# ILIZAROV_2.net
KiCad netlist of a schematic drawn in EAGLE
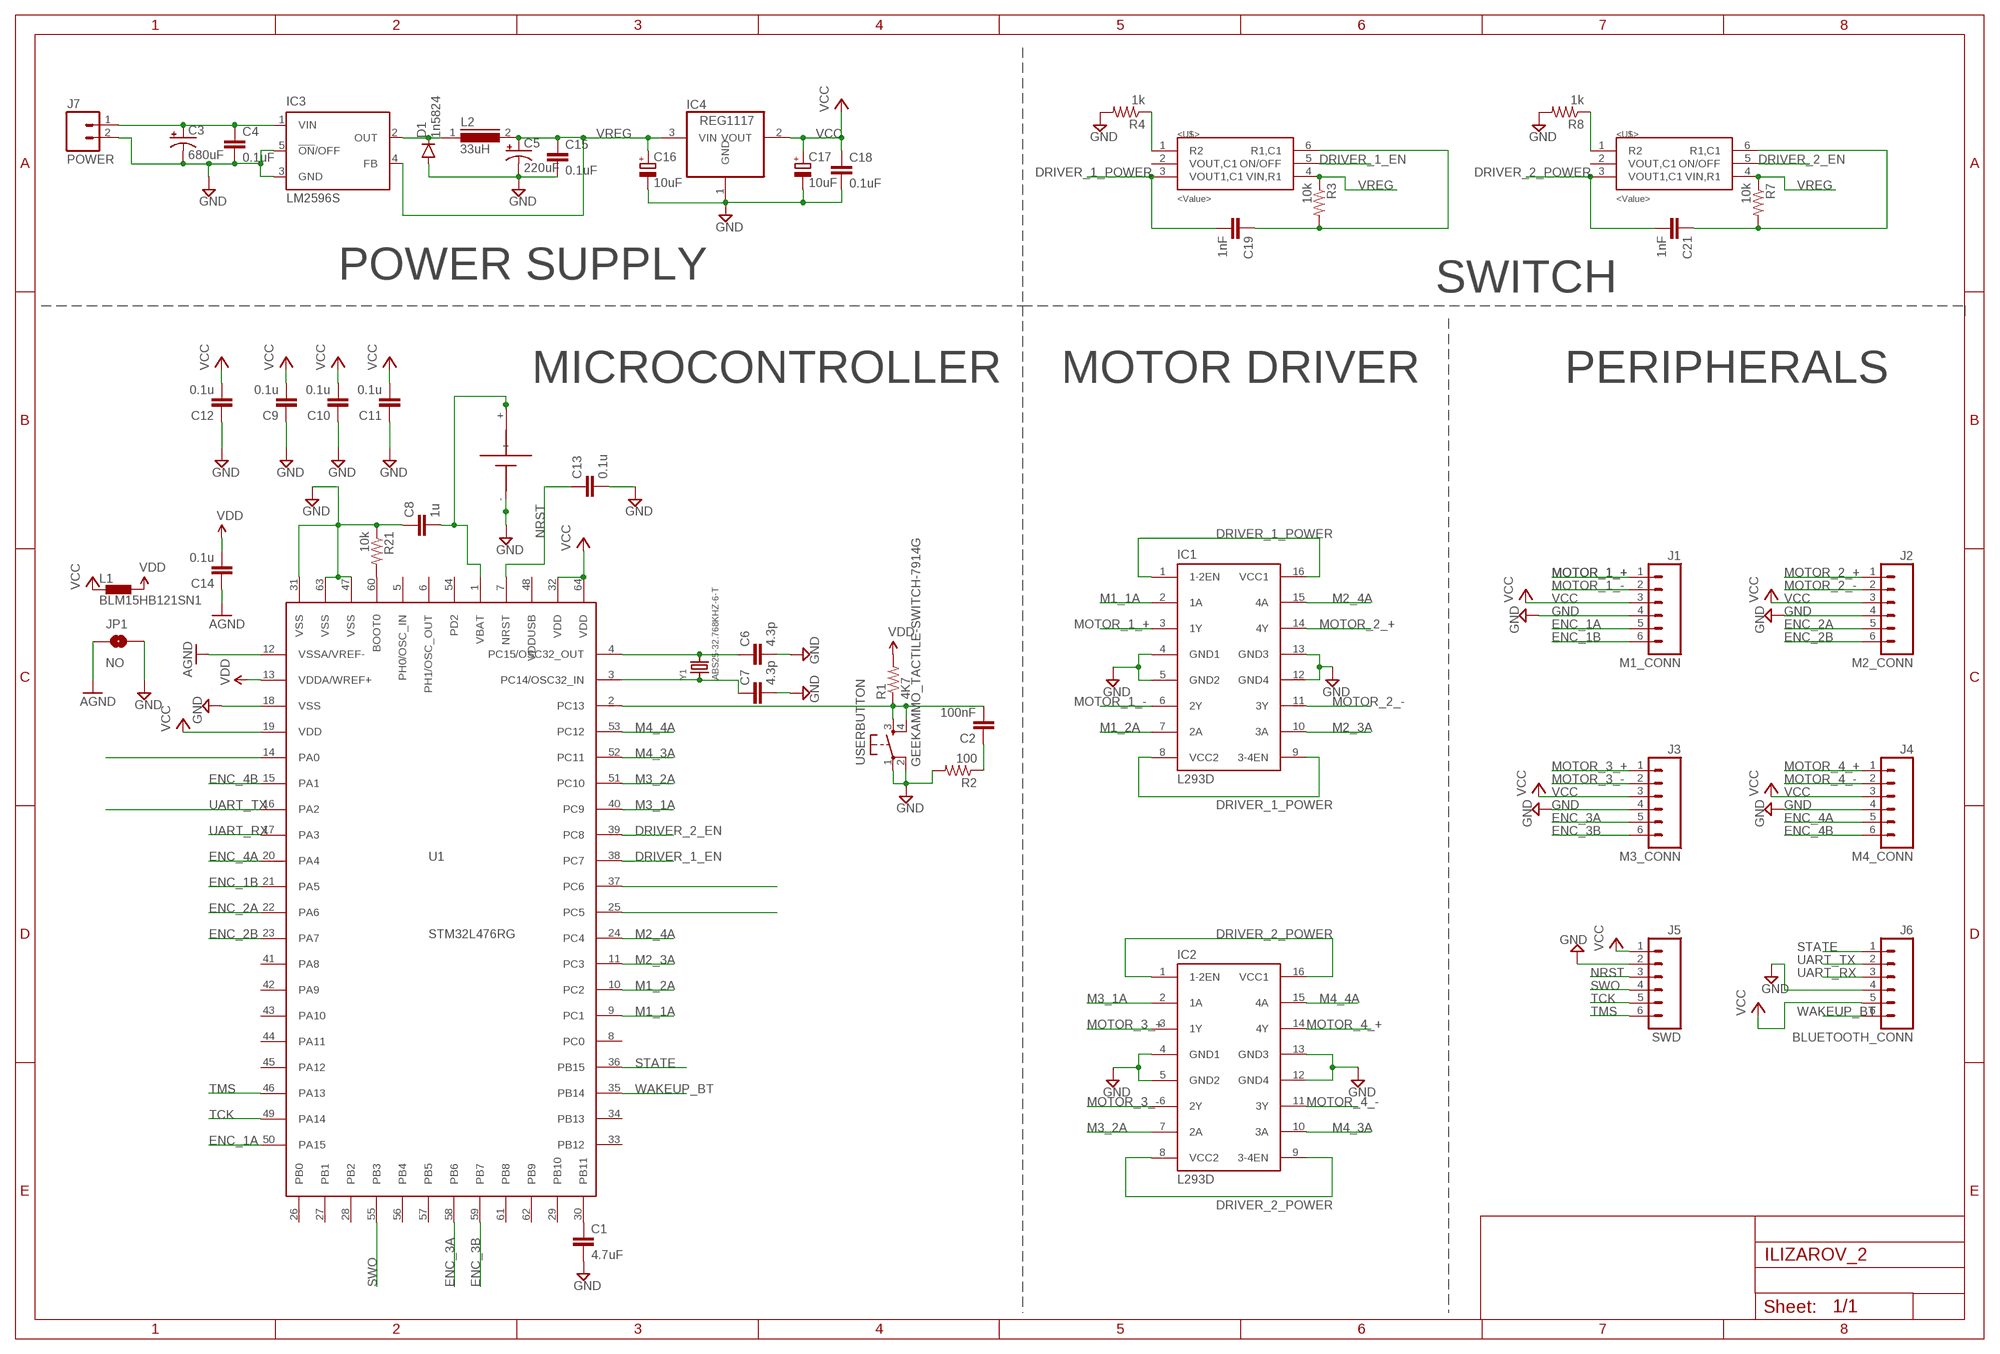
[diagram p0: schematic, sheet 1]

(export (version "E")
  (design (tool "Eeschema 10.0.6"))
  (components
    (comp (ref "BLUETOOTH_CONN")
      (value "J6")
      (footprint "eagle-import:06P")
      (libsource (lib "eagle-import") (part "M06"))
    )
    (comp (ref "C1")
      (value "4.7uF")
      (footprint "eagle-import:1206")
      (libsource (lib "eagle-import") (part "CAP1206"))
    )
    (comp (ref "C2")
      (value "100nF")
      (footprint "eagle-import:C0805")
      (libsource (lib "eagle-import") (part "C-EUC0805"))
    )
    (comp (ref "C3")
      (value "680uF")
      (footprint "eagle-import:140CLH-1010")
      (libsource (lib "eagle-import") (part "CPOL-US140CLH-1010"))
    )
    (comp (ref "C4")
      (value "0.1uF")
      (footprint "eagle-import:SPARKFUN-CAPACITORS_1206")
      (libsource (lib "eagle-import") (part "SPARKFUN-CAPACITORS_CAP1206"))
    )
    (comp (ref "C5")
      (value "220uF")
      (footprint "eagle-import:140CLH-1010")
      (libsource (lib "eagle-import") (part "CPOL-US140CLH-1010"))
    )
    (comp (ref "C6")
      (value "4.3p")
      (footprint "eagle-import:C0805")
      (libsource (lib "eagle-import") (part "C-EUC0805"))
    )
    (comp (ref "C7")
      (value "4.3p")
      (footprint "eagle-import:C0805")
      (libsource (lib "eagle-import") (part "C-EUC0805"))
    )
    (comp (ref "C8")
      (value "1u")
      (footprint "eagle-import:C0805")
      (libsource (lib "eagle-import") (part "C-EUC0805"))
    )
    (comp (ref "C9")
      (value "0.1u")
      (footprint "eagle-import:C0805")
      (libsource (lib "eagle-import") (part "C-EUC0805"))
    )
    (comp (ref "C10")
      (value "0.1u")
      (footprint "eagle-import:C0805")
      (libsource (lib "eagle-import") (part "C-EUC0805"))
    )
    (comp (ref "C11")
      (value "0.1u")
      (footprint "eagle-import:C0805")
      (libsource (lib "eagle-import") (part "C-EUC0805"))
    )
    (comp (ref "C12")
      (value "0.1u")
      (footprint "eagle-import:C0805")
      (libsource (lib "eagle-import") (part "C-EUC0805"))
    )
    (comp (ref "C13")
      (value "0.1u")
      (footprint "eagle-import:C0805")
      (libsource (lib "eagle-import") (part "C-EUC0805"))
    )
    (comp (ref "C14")
      (value "0.1u")
      (footprint "eagle-import:C0805")
      (libsource (lib "eagle-import") (part "C-EUC0805"))
    )
    (comp (ref "C15")
      (value "0.1uF")
      (footprint "eagle-import:SPARKFUN-CAPACITORS_1206")
      (libsource (lib "eagle-import") (part "SPARKFUN-CAPACITORS_CAP1206"))
    )
    (comp (ref "C16")
      (value "10uF")
      (footprint "eagle-import:SMC_C")
      (libsource (lib "eagle-import") (part "CPOL-EUSMCC"))
    )
    (comp (ref "C17")
      (value "10uF")
      (footprint "eagle-import:SMC_C")
      (libsource (lib "eagle-import") (part "CPOL-EUSMCC"))
    )
    (comp (ref "C18")
      (value "0.1uF")
      (footprint "eagle-import:SPARKFUN-CAPACITORS_1206")
      (libsource (lib "eagle-import") (part "SPARKFUN-CAPACITORS_CAP1206"))
    )
    (comp (ref "C19")
      (value "1nF")
      (footprint "eagle-import:C1206")
      (libsource (lib "eagle-import") (part "C-EUC1206"))
    )
    (comp (ref "C21")
      (value "1nF")
      (footprint "eagle-import:C1206")
      (libsource (lib "eagle-import") (part "C-EUC1206"))
    )
    (comp (ref "D1")
      (value "1n5824")
      (footprint "eagle-import:SPARKFUN-DISCRETESEMI_SOD-123")
      (libsource (lib "eagle-import") (part "SPARKFUN-DISCRETESEMI_DIODESOD123"))
    )
    (comp (ref "IC1")
      (value "L293D")
      (footprint "eagle-import:DIL16")
      (libsource (lib "eagle-import") (part "L293D"))
    )
    (comp (ref "IC2")
      (value "L293D")
      (footprint "eagle-import:DIL16")
      (libsource (lib "eagle-import") (part "L293D"))
    )
    (comp (ref "IC3")
      (value "LM2596S")
      (footprint "eagle-import:TO263-5")
      (fields (field (name "MF") "NATIONAL SEMICONDUCTOR") (field (name "MPN") "LM2596S-ADJ/NOPB"))
      (libsource (lib "eagle-import") (part "LM2596S"))
    )
    (comp (ref "IC4")
      (value "REG1117")
      (footprint "eagle-import:SOT223")
      (libsource (lib "eagle-import") (part "REG1117"))
    )
    (comp (ref "JP1")
      (value "NO")
      (footprint "eagle-import:PAD-JUMPER-2-NO_NO_SILK")
      (libsource (lib "eagle-import") (part "JUMPER-PAD-2-NO"))
    )
    (comp (ref "L1")
      (value "BLM15HB121SN1")
      (footprint "eagle-import:0402")
      (libsource (lib "eagle-import") (part "BLM15HB121SN1"))
    )
    (comp (ref "L2")
      (value "33uH")
      (footprint "eagle-import:DR125")
      (libsource (lib "eagle-import") (part "DR125"))
    )
    (comp (ref "M1_CONN")
      (value "J1")
      (footprint "eagle-import:06P")
      (libsource (lib "eagle-import") (part "M06"))
    )
    (comp (ref "M2_CONN")
      (value "J2")
      (footprint "eagle-import:06P")
      (libsource (lib "eagle-import") (part "M06"))
    )
    (comp (ref "M3_CONN")
      (value "J3")
      (footprint "eagle-import:06P")
      (libsource (lib "eagle-import") (part "M06"))
    )
    (comp (ref "M4_CONN")
      (value "J4")
      (footprint "eagle-import:06P")
      (libsource (lib "eagle-import") (part "M06"))
    )
    (comp (ref "POWER")
      (value "J7")
      (footprint "eagle-import:02P")
      (libsource (lib "eagle-import") (part "M02"))
    )
    (comp (ref "R1")
      (value "4K7")
      (footprint "eagle-import:1206")
      (libsource (lib "eagle-import") (part "RESISTOR1206"))
    )
    (comp (ref "R2")
      (value "100")
      (footprint "eagle-import:1206")
      (libsource (lib "eagle-import") (part "RESISTOR1206"))
    )
    (comp (ref "R3")
      (value "10k")
      (footprint "eagle-import:1206")
      (libsource (lib "eagle-import") (part "RESISTOR1206"))
    )
    (comp (ref "R4")
      (value "1k")
      (footprint "eagle-import:1206")
      (libsource (lib "eagle-import") (part "RESISTOR1206"))
    )
    (comp (ref "R7")
      (value "10k")
      (footprint "eagle-import:1206")
      (libsource (lib "eagle-import") (part "RESISTOR1206"))
    )
    (comp (ref "R8")
      (value "1k")
      (footprint "eagle-import:1206")
      (libsource (lib "eagle-import") (part "RESISTOR1206"))
    )
    (comp (ref "R21")
      (value "10k")
      (footprint "eagle-import:M0805")
      (libsource (lib "eagle-import") (part "R-US_M0805"))
    )
    (comp (ref "SWD")
      (value "J5")
      (footprint "eagle-import:06P")
      (libsource (lib "eagle-import") (part "M06"))
    )
    (comp (ref "U$1")
      (value "MS920")
      (footprint "eagle-import:SMD")
      (libsource (lib "eagle-import") (part "MS920"))
    )
    (comp (ref "U$6")
      (value "FDC6330L")
      (footprint "eagle-import:SOT23-6")
      (libsource (lib "eagle-import") (part "FDC6330L"))
    )
    (comp (ref "U$7")
      (value "FDC6330L")
      (footprint "eagle-import:SOT23-6")
      (libsource (lib "eagle-import") (part "FDC6330L"))
    )
    (comp (ref "U1")
      (value "STM32L476RG")
      (footprint "eagle-import:LQFP-10X10-64")
      (libsource (lib "eagle-import") (part "STM32L476RG"))
    )
    (comp (ref "USERBUTTON")
      (value "GEEKAMMO_TACTILE-SWITCH-7914G")
      (footprint "eagle-import:GEEKAMMO_7914G")
      (libsource (lib "eagle-import") (part "GEEKAMMO_TACTILE-SWITCH-7914G"))
    )
    (comp (ref "Y1")
      (value "ABS25-32.768KHZ-6-T")
      (footprint "eagle-import:ABS25")
      (libsource (lib "eagle-import") (part "CRYSTAL.ABS25"))
    )
  )
  (nets
    (net (code "1") (name "/DRIVER_1_EN") (class "Default")
      (node (ref "U$7") (pin "5") (pinfunction "ON/OFF_5") (pintype "bidirectional"))
      (node (ref "U1") (pin "38") (pinfunction "PC7_38") (pintype "bidirectional"))
    )
    (net (code "2") (name "/DRIVER_1_POWER") (class "Default")
      (node (ref "C19") (pin "2") (pinfunction "2_2") (pintype "passive"))
      (node (ref "IC1") (pin "1") (pinfunction "1-2EN_1") (pintype "input"))
      (node (ref "IC1") (pin "16") (pinfunction "VCC1_16") (pintype "power_in"))
      (node (ref "IC1") (pin "8") (pinfunction "VCC2_8") (pintype "power_in"))
      (node (ref "IC1") (pin "9") (pinfunction "3-4EN_9") (pintype "input"))
      (node (ref "U$7") (pin "3") (pinfunction "VOUT1,C1_3") (pintype "bidirectional"))
    )
    (net (code "3") (name "/DRIVER_2_EN") (class "Default")
      (node (ref "U$6") (pin "5") (pinfunction "ON/OFF_5") (pintype "bidirectional"))
      (node (ref "U1") (pin "39") (pinfunction "PC8_39") (pintype "bidirectional"))
    )
    (net (code "4") (name "/DRIVER_2_POWER") (class "Default")
      (node (ref "C21") (pin "2") (pinfunction "2_2") (pintype "passive"))
      (node (ref "IC2") (pin "1") (pinfunction "1-2EN_1") (pintype "input"))
      (node (ref "IC2") (pin "16") (pinfunction "VCC1_16") (pintype "power_in"))
      (node (ref "IC2") (pin "8") (pinfunction "VCC2_8") (pintype "power_in"))
      (node (ref "IC2") (pin "9") (pinfunction "3-4EN_9") (pintype "input"))
      (node (ref "U$6") (pin "3") (pinfunction "VOUT1,C1_3") (pintype "bidirectional"))
    )
    (net (code "5") (name "/ENC_1A") (class "Default")
      (node (ref "M1_CONN") (pin "5") (pinfunction "5_5") (pintype "passive"))
      (node (ref "U1") (pin "50") (pinfunction "PA15_50") (pintype "bidirectional"))
    )
    (net (code "6") (name "/ENC_1B") (class "Default")
      (node (ref "M1_CONN") (pin "6") (pinfunction "6_6") (pintype "passive"))
      (node (ref "U1") (pin "21") (pinfunction "PA5_21") (pintype "bidirectional"))
    )
    (net (code "7") (name "/ENC_2A") (class "Default")
      (node (ref "M2_CONN") (pin "5") (pinfunction "5_5") (pintype "passive"))
      (node (ref "U1") (pin "22") (pinfunction "PA6_22") (pintype "bidirectional"))
    )
    (net (code "8") (name "/ENC_2B") (class "Default")
      (node (ref "M2_CONN") (pin "6") (pinfunction "6_6") (pintype "passive"))
      (node (ref "U1") (pin "23") (pinfunction "PA7_23") (pintype "bidirectional"))
    )
    (net (code "9") (name "/ENC_3A") (class "Default")
      (node (ref "M3_CONN") (pin "5") (pinfunction "5_5") (pintype "passive"))
      (node (ref "U1") (pin "58") (pinfunction "PB6_58") (pintype "bidirectional"))
    )
    (net (code "10") (name "/ENC_3B") (class "Default")
      (node (ref "M3_CONN") (pin "6") (pinfunction "6_6") (pintype "passive"))
      (node (ref "U1") (pin "59") (pinfunction "PB7_59") (pintype "bidirectional"))
    )
    (net (code "11") (name "/ENC_4A") (class "Default")
      (node (ref "M4_CONN") (pin "5") (pinfunction "5_5") (pintype "passive"))
      (node (ref "U1") (pin "20") (pinfunction "PA4_20") (pintype "bidirectional"))
    )
    (net (code "12") (name "/ENC_4B") (class "Default")
      (node (ref "M4_CONN") (pin "6") (pinfunction "6_6") (pintype "passive"))
      (node (ref "U1") (pin "15") (pinfunction "PA1_15") (pintype "bidirectional"))
    )
    (net (code "13") (name "/M1_1A") (class "Default")
      (node (ref "IC1") (pin "2") (pinfunction "1A_2") (pintype "input"))
      (node (ref "U1") (pin "9") (pinfunction "PC1_9") (pintype "bidirectional"))
    )
    (net (code "14") (name "/M1_2A") (class "Default")
      (node (ref "IC1") (pin "7") (pinfunction "2A_7") (pintype "input"))
      (node (ref "U1") (pin "10") (pinfunction "PC2_10") (pintype "bidirectional"))
    )
    (net (code "15") (name "/M2_3A") (class "Default")
      (node (ref "IC1") (pin "10") (pinfunction "3A_10") (pintype "input"))
      (node (ref "U1") (pin "11") (pinfunction "PC3_11") (pintype "bidirectional"))
    )
    (net (code "16") (name "/M2_4A") (class "Default")
      (node (ref "IC1") (pin "15") (pinfunction "4A_15") (pintype "input"))
      (node (ref "U1") (pin "24") (pinfunction "PC4_24") (pintype "bidirectional"))
    )
    (net (code "17") (name "/M3_1A") (class "Default")
      (node (ref "IC2") (pin "2") (pinfunction "1A_2") (pintype "input"))
      (node (ref "U1") (pin "40") (pinfunction "PC9_40") (pintype "bidirectional"))
    )
    (net (code "18") (name "/M3_2A") (class "Default")
      (node (ref "IC2") (pin "7") (pinfunction "2A_7") (pintype "input"))
      (node (ref "U1") (pin "51") (pinfunction "PC10_51") (pintype "bidirectional"))
    )
    (net (code "19") (name "/M4_3A") (class "Default")
      (node (ref "IC2") (pin "10") (pinfunction "3A_10") (pintype "input"))
      (node (ref "U1") (pin "52") (pinfunction "PC11_52") (pintype "bidirectional"))
    )
    (net (code "20") (name "/M4_4A") (class "Default")
      (node (ref "IC2") (pin "15") (pinfunction "4A_15") (pintype "input"))
      (node (ref "U1") (pin "53") (pinfunction "PC12_53") (pintype "bidirectional"))
    )
    (net (code "21") (name "/MOTOR_1_+") (class "Default")
      (node (ref "IC1") (pin "3") (pinfunction "1Y_3") (pintype "output"))
      (node (ref "M1_CONN") (pin "1") (pinfunction "1_1") (pintype "passive"))
    )
    (net (code "22") (name "/MOTOR_1_-") (class "Default")
      (node (ref "IC1") (pin "6") (pinfunction "2Y_6") (pintype "output"))
      (node (ref "M1_CONN") (pin "2") (pinfunction "2_2") (pintype "passive"))
    )
    (net (code "23") (name "/MOTOR_2_+") (class "Default")
      (node (ref "IC1") (pin "14") (pinfunction "4Y_14") (pintype "output"))
      (node (ref "M2_CONN") (pin "1") (pinfunction "1_1") (pintype "passive"))
    )
    (net (code "24") (name "/MOTOR_2_-") (class "Default")
      (node (ref "IC1") (pin "11") (pinfunction "3Y_11") (pintype "output"))
      (node (ref "M2_CONN") (pin "2") (pinfunction "2_2") (pintype "passive"))
    )
    (net (code "25") (name "/MOTOR_3_+") (class "Default")
      (node (ref "IC2") (pin "3") (pinfunction "1Y_3") (pintype "output"))
      (node (ref "M3_CONN") (pin "1") (pinfunction "1_1") (pintype "passive"))
    )
    (net (code "26") (name "/MOTOR_3_-") (class "Default")
      (node (ref "IC2") (pin "6") (pinfunction "2Y_6") (pintype "output"))
      (node (ref "M3_CONN") (pin "2") (pinfunction "2_2") (pintype "passive"))
    )
    (net (code "27") (name "/MOTOR_4_+") (class "Default")
      (node (ref "IC2") (pin "14") (pinfunction "4Y_14") (pintype "output"))
      (node (ref "M4_CONN") (pin "1") (pinfunction "1_1") (pintype "passive"))
    )
    (net (code "28") (name "/MOTOR_4_-") (class "Default")
      (node (ref "IC2") (pin "11") (pinfunction "3Y_11") (pintype "output"))
      (node (ref "M4_CONN") (pin "2") (pinfunction "2_2") (pintype "passive"))
    )
    (net (code "29") (name "/NC") (class "Default")
      (node (ref "U1") (pin "14") (pinfunction "PA0_14") (pintype "bidirectional"))
      (node (ref "U1") (pin "25") (pinfunction "PC5_25") (pintype "bidirectional"))
      (node (ref "U1") (pin "37") (pinfunction "PC6_37") (pintype "bidirectional"))
    )
    (net (code "30") (name "/NRST") (class "Default")
      (node (ref "C13") (pin "1") (pinfunction "1_1") (pintype "passive"))
      (node (ref "SWD") (pin "3") (pinfunction "3_3") (pintype "passive"))
      (node (ref "U1") (pin "7") (pinfunction "NRST_7") (pintype "bidirectional"))
    )
    (net (code "31") (name "/STATE") (class "Default")
      (node (ref "BLUETOOTH_CONN") (pin "1") (pinfunction "1_1") (pintype "passive"))
      (node (ref "U1") (pin "36") (pinfunction "PB15_36") (pintype "bidirectional"))
    )
    (net (code "32") (name "/SWO") (class "Default")
      (node (ref "SWD") (pin "4") (pinfunction "4_4") (pintype "passive"))
      (node (ref "U1") (pin "55") (pinfunction "PB3_55") (pintype "bidirectional"))
    )
    (net (code "33") (name "/TCK") (class "Default")
      (node (ref "SWD") (pin "5") (pinfunction "5_5") (pintype "passive"))
      (node (ref "U1") (pin "49") (pinfunction "PA14_49") (pintype "bidirectional"))
    )
    (net (code "34") (name "/TMS") (class "Default")
      (node (ref "SWD") (pin "6") (pinfunction "6_6") (pintype "passive"))
      (node (ref "U1") (pin "46") (pinfunction "PA13_46") (pintype "bidirectional"))
    )
    (net (code "35") (name "/UART_RX") (class "Default")
      (node (ref "BLUETOOTH_CONN") (pin "3") (pinfunction "3_3") (pintype "passive"))
      (node (ref "U1") (pin "17") (pinfunction "PA3_17") (pintype "bidirectional"))
    )
    (net (code "36") (name "/UART_TX") (class "Default")
      (node (ref "BLUETOOTH_CONN") (pin "2") (pinfunction "2_2") (pintype "passive"))
      (node (ref "U1") (pin "16") (pinfunction "PA2_16") (pintype "bidirectional"))
    )
    (net (code "37") (name "/VDDUSB") (class "Default")
      (node (ref "U1") (pin "48") (pinfunction "VDDUSB_48") (pintype "power_in"))
    )
    (net (code "38") (name "/VREG") (class "Default")
      (node (ref "C15") (pin "1") (pinfunction "1_1") (pintype "passive"))
      (node (ref "C16") (pin "+") (pinfunction "+_+") (pintype "passive"))
      (node (ref "C5") (pin "+") (pinfunction "+_+") (pintype "passive"))
      (node (ref "IC3") (pin "4") (pinfunction "FB_4") (pintype "input"))
      (node (ref "IC4") (pin "3") (pinfunction "VIN_3") (pintype "input"))
      (node (ref "L2") (pin "2") (pinfunction "2_2") (pintype "passive"))
      (node (ref "R3") (pin "1") (pinfunction "1_1") (pintype "passive"))
      (node (ref "R7") (pin "1") (pinfunction "1_1") (pintype "passive"))
      (node (ref "U$6") (pin "4") (pinfunction "VIN,R1_4") (pintype "bidirectional"))
      (node (ref "U$7") (pin "4") (pinfunction "VIN,R1_4") (pintype "bidirectional"))
    )
    (net (code "39") (name "/WAKEUP_BT") (class "Default")
      (node (ref "BLUETOOTH_CONN") (pin "6") (pinfunction "6_6") (pintype "passive"))
      (node (ref "U1") (pin "35") (pinfunction "PB14_35") (pintype "bidirectional"))
    )
    (net (code "40") (name "AGND") (class "Default")
      (node (ref "C14") (pin "1") (pinfunction "1_1") (pintype "passive"))
      (node (ref "JP1") (pin "1") (pinfunction "1_1") (pintype "passive"))
      (node (ref "U1") (pin "12") (pinfunction "VSSA/VREF-_12") (pintype "power_in"))
    )
    (net (code "41") (name "GND") (class "Default")
      (node (ref "BLUETOOTH_CONN") (pin "4") (pinfunction "4_4") (pintype "passive"))
      (node (ref "C1") (pin "2") (pinfunction "2_2") (pintype "passive"))
      (node (ref "C10") (pin "1") (pinfunction "1_1") (pintype "passive"))
      (node (ref "C11") (pin "1") (pinfunction "1_1") (pintype "passive"))
      (node (ref "C12") (pin "1") (pinfunction "1_1") (pintype "passive"))
      (node (ref "C13") (pin "2") (pinfunction "2_2") (pintype "passive"))
      (node (ref "C15") (pin "2") (pinfunction "2_2") (pintype "passive"))
      (node (ref "C16") (pin "-") (pinfunction "-_-") (pintype "passive"))
      (node (ref "C17") (pin "-") (pinfunction "-_-") (pintype "passive"))
      (node (ref "C18") (pin "2") (pinfunction "2_2") (pintype "passive"))
      (node (ref "C3") (pin "-") (pinfunction "-_-") (pintype "passive"))
      (node (ref "C4") (pin "2") (pinfunction "2_2") (pintype "passive"))
      (node (ref "C5") (pin "-") (pinfunction "-_-") (pintype "passive"))
      (node (ref "C6") (pin "2") (pinfunction "2_2") (pintype "passive"))
      (node (ref "C7") (pin "2") (pinfunction "2_2") (pintype "passive"))
      (node (ref "C8") (pin "1") (pinfunction "1_1") (pintype "passive"))
      (node (ref "C9") (pin "1") (pinfunction "1_1") (pintype "passive"))
      (node (ref "D1") (pin "A") (pinfunction "A_A") (pintype "passive"))
      (node (ref "IC1") (pin "12") (pinfunction "GND4_12") (pintype "power_in"))
      (node (ref "IC1") (pin "13") (pinfunction "GND3_13") (pintype "power_in"))
      (node (ref "IC1") (pin "4") (pinfunction "GND1_4") (pintype "power_in"))
      (node (ref "IC1") (pin "5") (pinfunction "GND2_5") (pintype "power_in"))
      (node (ref "IC2") (pin "12") (pinfunction "GND4_12") (pintype "power_in"))
      (node (ref "IC2") (pin "13") (pinfunction "GND3_13") (pintype "power_in"))
      (node (ref "IC2") (pin "4") (pinfunction "GND1_4") (pintype "power_in"))
      (node (ref "IC2") (pin "5") (pinfunction "GND2_5") (pintype "power_in"))
      (node (ref "IC3") (pin "3") (pinfunction "GND_3") (pintype "power_in"))
      (node (ref "IC3") (pin "5") (pinfunction "~{ON}/OFF_5") (pintype "input"))
      (node (ref "IC4") (pin "1") (pinfunction "GND_1") (pintype "power_in"))
      (node (ref "JP1") (pin "2") (pinfunction "2_2") (pintype "passive"))
      (node (ref "M1_CONN") (pin "4") (pinfunction "4_4") (pintype "passive"))
      (node (ref "M2_CONN") (pin "4") (pinfunction "4_4") (pintype "passive"))
      (node (ref "M3_CONN") (pin "4") (pinfunction "4_4") (pintype "passive"))
      (node (ref "M4_CONN") (pin "4") (pinfunction "4_4") (pintype "passive"))
      (node (ref "POWER") (pin "2") (pinfunction "2_2") (pintype "passive"))
      (node (ref "R2") (pin "2") (pinfunction "2_2") (pintype "passive"))
      (node (ref "R21") (pin "1") (pinfunction "1_1") (pintype "passive"))
      (node (ref "R4") (pin "2") (pinfunction "2_2") (pintype "passive"))
      (node (ref "R8") (pin "2") (pinfunction "2_2") (pintype "passive"))
      (node (ref "SWD") (pin "2") (pinfunction "2_2") (pintype "passive"))
      (node (ref "U$1") (pin "-") (pinfunction "-_-") (pintype "bidirectional"))
      (node (ref "U1") (pin "18") (pinfunction "VSS_18") (pintype "power_in"))
      (node (ref "U1") (pin "31") (pinfunction "VSS_31") (pintype "power_in"))
      (node (ref "U1") (pin "47") (pinfunction "VSS_47") (pintype "power_in"))
      (node (ref "U1") (pin "63") (pinfunction "VSS_63") (pintype "power_in"))
      (node (ref "USERBUTTON") (pin "1") (pinfunction "1_1") (pintype "passive"))
      (node (ref "USERBUTTON") (pin "2") (pinfunction "2_2") (pintype "passive"))
    )
    (net (code "42") (name "Net-(C2-Pad1)") (class "Default")
      (node (ref "C2") (pin "1") (pinfunction "1_1") (pintype "passive"))
      (node (ref "R2") (pin "1") (pinfunction "1_1") (pintype "passive"))
    )
    (net (code "43") (name "Net-(IC3-OUT)") (class "Default")
      (node (ref "D1") (pin "C") (pinfunction "C_C") (pintype "passive"))
      (node (ref "IC3") (pin "2") (pinfunction "OUT_2") (pintype "output"))
      (node (ref "L2") (pin "1") (pinfunction "1_1") (pintype "passive"))
    )
    (net (code "44") (name "Net-(IC3-VIN)") (class "Default")
      (node (ref "C3") (pin "+") (pinfunction "+_+") (pintype "passive"))
      (node (ref "C4") (pin "1") (pinfunction "1_1") (pintype "passive"))
      (node (ref "IC3") (pin "1") (pinfunction "VIN_1") (pintype "input"))
      (node (ref "POWER") (pin "1") (pinfunction "1_1") (pintype "passive"))
    )
    (net (code "45") (name "Net-(U$6-R1,C1)") (class "Default")
      (node (ref "C21") (pin "1") (pinfunction "1_1") (pintype "passive"))
      (node (ref "R7") (pin "2") (pinfunction "2_2") (pintype "passive"))
      (node (ref "U$6") (pin "6") (pinfunction "R1,C1_6") (pintype "bidirectional"))
    )
    (net (code "46") (name "Net-(U$6-R2)") (class "Default")
      (node (ref "R8") (pin "1") (pinfunction "1_1") (pintype "passive"))
      (node (ref "U$6") (pin "1") (pinfunction "R2_1") (pintype "bidirectional"))
    )
    (net (code "47") (name "Net-(U$7-R1,C1)") (class "Default")
      (node (ref "C19") (pin "1") (pinfunction "1_1") (pintype "passive"))
      (node (ref "R3") (pin "2") (pinfunction "2_2") (pintype "passive"))
      (node (ref "U$7") (pin "6") (pinfunction "R1,C1_6") (pintype "bidirectional"))
    )
    (net (code "48") (name "Net-(U$7-R2)") (class "Default")
      (node (ref "R4") (pin "1") (pinfunction "1_1") (pintype "passive"))
      (node (ref "U$7") (pin "1") (pinfunction "R2_1") (pintype "bidirectional"))
    )
    (net (code "49") (name "Net-(U1-BOOT0)") (class "Default")
      (node (ref "R21") (pin "2") (pinfunction "2_2") (pintype "passive"))
      (node (ref "U1") (pin "60") (pinfunction "BOOT0_60") (pintype "bidirectional"))
    )
    (net (code "50") (name "Net-(U1-PB11)") (class "Default")
      (node (ref "C1") (pin "1") (pinfunction "1_1") (pintype "passive"))
      (node (ref "U1") (pin "30") (pinfunction "PB11_30") (pintype "bidirectional"))
    )
    (net (code "51") (name "Net-(U1-PC13)") (class "Default")
      (node (ref "C2") (pin "2") (pinfunction "2_2") (pintype "passive"))
      (node (ref "R1") (pin "1") (pinfunction "1_1") (pintype "passive"))
      (node (ref "U1") (pin "2") (pinfunction "PC13_2") (pintype "bidirectional"))
      (node (ref "USERBUTTON") (pin "3") (pinfunction "3_3") (pintype "passive"))
      (node (ref "USERBUTTON") (pin "4") (pinfunction "4_4") (pintype "passive"))
    )
    (net (code "52") (name "Net-(U1-PC14{slash}OSC32_IN)") (class "Default")
      (node (ref "C7") (pin "1") (pinfunction "1_1") (pintype "passive"))
      (node (ref "U1") (pin "3") (pinfunction "PC14/OSC32_IN_3") (pintype "bidirectional"))
      (node (ref "Y1") (pin "1") (pinfunction "1_1") (pintype "passive"))
    )
    (net (code "53") (name "Net-(U1-PC15{slash}OSC32_OUT)") (class "Default")
      (node (ref "C6") (pin "1") (pinfunction "1_1") (pintype "passive"))
      (node (ref "U1") (pin "4") (pinfunction "PC15/OSC32_OUT_4") (pintype "bidirectional"))
      (node (ref "Y1") (pin "4") (pinfunction "2_4") (pintype "passive"))
    )
    (net (code "54") (name "Net-(U1-VBAT)") (class "Default")
      (node (ref "C8") (pin "2") (pinfunction "2_2") (pintype "passive"))
      (node (ref "U$1") (pin "+") (pinfunction "+_+") (pintype "bidirectional"))
      (node (ref "U1") (pin "1") (pinfunction "VBAT_1") (pintype "bidirectional"))
    )
    (net (code "55") (name "VCC") (class "Default")
      (node (ref "BLUETOOTH_CONN") (pin "5") (pinfunction "5_5") (pintype "passive"))
      (node (ref "C10") (pin "2") (pinfunction "2_2") (pintype "passive"))
      (node (ref "C11") (pin "2") (pinfunction "2_2") (pintype "passive"))
      (node (ref "C12") (pin "2") (pinfunction "2_2") (pintype "passive"))
      (node (ref "C17") (pin "+") (pinfunction "+_+") (pintype "passive"))
      (node (ref "C18") (pin "1") (pinfunction "1_1") (pintype "passive"))
      (node (ref "C9") (pin "2") (pinfunction "2_2") (pintype "passive"))
      (node (ref "IC4") (pin "2") (pinfunction "VOUT_2") (pintype "output"))
      (node (ref "L1") (pin "1") (pinfunction "1_1") (pintype "passive"))
      (node (ref "M1_CONN") (pin "3") (pinfunction "3_3") (pintype "passive"))
      (node (ref "M2_CONN") (pin "3") (pinfunction "3_3") (pintype "passive"))
      (node (ref "M3_CONN") (pin "3") (pinfunction "3_3") (pintype "passive"))
      (node (ref "M4_CONN") (pin "3") (pinfunction "3_3") (pintype "passive"))
      (node (ref "SWD") (pin "1") (pinfunction "1_1") (pintype "passive"))
      (node (ref "U1") (pin "19") (pinfunction "VDD_19") (pintype "power_in"))
      (node (ref "U1") (pin "32") (pinfunction "VDD_32") (pintype "power_in"))
      (node (ref "U1") (pin "64") (pinfunction "VDD_64") (pintype "power_in"))
    )
    (net (code "56") (name "VDD") (class "Default")
      (node (ref "C14") (pin "2") (pinfunction "2_2") (pintype "passive"))
      (node (ref "L1") (pin "2") (pinfunction "2_2") (pintype "passive"))
      (node (ref "R1") (pin "2") (pinfunction "2_2") (pintype "passive"))
      (node (ref "U1") (pin "13") (pinfunction "VDDA/WREF+_13") (pintype "power_in"))
    )
    (net (code "57") (name "unconnected-(U$6-VOUT,C1-Pad2)") (class "Default")
      (node (ref "U$6") (pin "2") (pinfunction "VOUT,C1_2") (pintype "bidirectional"))
    )
    (net (code "58") (name "unconnected-(U$7-VOUT,C1-Pad2)") (class "Default")
      (node (ref "U$7") (pin "2") (pinfunction "VOUT,C1_2") (pintype "bidirectional"))
    )
    (net (code "59") (name "unconnected-(U1-PA8-Pad41)") (class "Default")
      (node (ref "U1") (pin "41") (pinfunction "PA8_41") (pintype "bidirectional"))
    )
    (net (code "60") (name "unconnected-(U1-PA9-Pad42)") (class "Default")
      (node (ref "U1") (pin "42") (pinfunction "PA9_42") (pintype "bidirectional"))
    )
    (net (code "61") (name "unconnected-(U1-PA10-Pad43)") (class "Default")
      (node (ref "U1") (pin "43") (pinfunction "PA10_43") (pintype "bidirectional"))
    )
    (net (code "62") (name "unconnected-(U1-PA11-Pad44)") (class "Default")
      (node (ref "U1") (pin "44") (pinfunction "PA11_44") (pintype "bidirectional"))
    )
    (net (code "63") (name "unconnected-(U1-PA12-Pad45)") (class "Default")
      (node (ref "U1") (pin "45") (pinfunction "PA12_45") (pintype "bidirectional"))
    )
    (net (code "64") (name "unconnected-(U1-PB0-Pad26)") (class "Default")
      (node (ref "U1") (pin "26") (pinfunction "PB0_26") (pintype "bidirectional"))
    )
    (net (code "65") (name "unconnected-(U1-PB1-Pad27)") (class "Default")
      (node (ref "U1") (pin "27") (pinfunction "PB1_27") (pintype "bidirectional"))
    )
    (net (code "66") (name "unconnected-(U1-PB2-Pad28)") (class "Default")
      (node (ref "U1") (pin "28") (pinfunction "PB2_28") (pintype "bidirectional"))
    )
    (net (code "67") (name "unconnected-(U1-PB4-Pad56)") (class "Default")
      (node (ref "U1") (pin "56") (pinfunction "PB4_56") (pintype "bidirectional"))
    )
    (net (code "68") (name "unconnected-(U1-PB5-Pad57)") (class "Default")
      (node (ref "U1") (pin "57") (pinfunction "PB5_57") (pintype "bidirectional"))
    )
    (net (code "69") (name "unconnected-(U1-PB8-Pad61)") (class "Default")
      (node (ref "U1") (pin "61") (pinfunction "PB8_61") (pintype "bidirectional"))
    )
    (net (code "70") (name "unconnected-(U1-PB9-Pad62)") (class "Default")
      (node (ref "U1") (pin "62") (pinfunction "PB9_62") (pintype "bidirectional"))
    )
    (net (code "71") (name "unconnected-(U1-PB10-Pad29)") (class "Default")
      (node (ref "U1") (pin "29") (pinfunction "PB10_29") (pintype "bidirectional"))
    )
    (net (code "72") (name "unconnected-(U1-PB12-Pad33)") (class "Default")
      (node (ref "U1") (pin "33") (pinfunction "PB12_33") (pintype "bidirectional"))
    )
    (net (code "73") (name "unconnected-(U1-PB13-Pad34)") (class "Default")
      (node (ref "U1") (pin "34") (pinfunction "PB13_34") (pintype "bidirectional"))
    )
    (net (code "74") (name "unconnected-(U1-PC0-Pad8)") (class "Default")
      (node (ref "U1") (pin "8") (pinfunction "PC0_8") (pintype "bidirectional"))
    )
    (net (code "75") (name "unconnected-(U1-PD2-Pad54)") (class "Default")
      (node (ref "U1") (pin "54") (pinfunction "PD2_54") (pintype "bidirectional"))
    )
    (net (code "76") (name "unconnected-(U1-PH0{slash}OSC_IN-Pad5)") (class "Default")
      (node (ref "U1") (pin "5") (pinfunction "PH0/OSC_IN_5") (pintype "bidirectional"))
    )
    (net (code "77") (name "unconnected-(U1-PH1{slash}OSC_OUT-Pad6)") (class "Default")
      (node (ref "U1") (pin "6") (pinfunction "PH1/OSC_OUT_6") (pintype "bidirectional"))
    )
  )
)
